# LED_Running_Final.net
KiCad netlist of a schematic drawn in Altium Designer
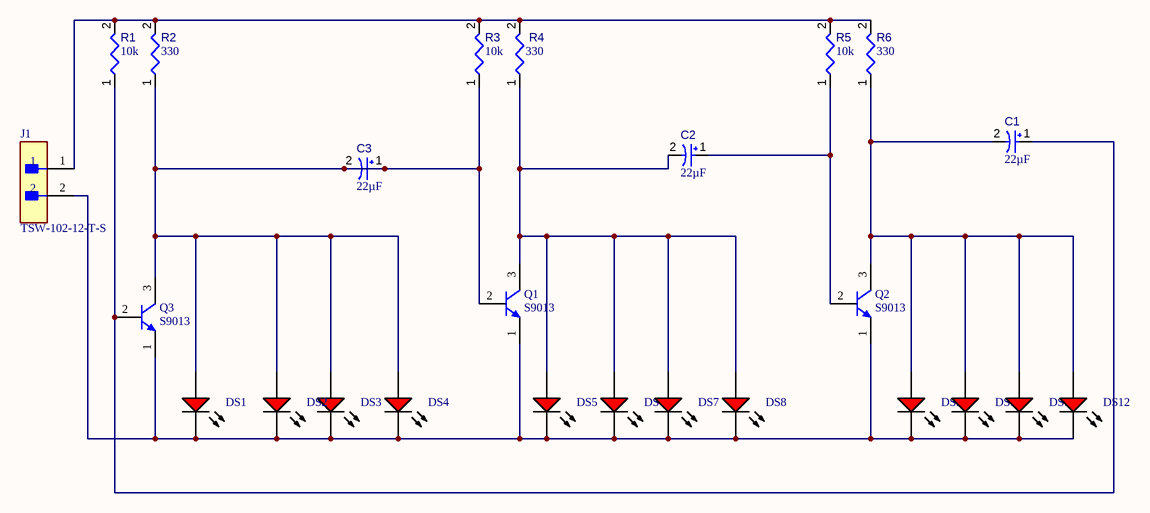
[diagram p0: LED_Running_Final.SchDoc]

(export (version "E")
  (design (tool "Eeschema 10.0.6"))
  (components
    (comp (ref "C1")
      (value "22µF")
      (footprint "CAPPR55-250-1120X630X1220")
      (description "Aluminum Electrolytic Capacitor, 22 uF, +/- 20%, 100 V, -40 to 85 degC, 2-Pin THD, RoHS, Bulk")
      (fields (field (name "MANUFACTURER") "Panasonic") (field (name "TOLERANCE") "20%"))
      (libsource (lib "MD RAFIUL ISLAM") (part "CAP-P-2"))
    )
    (comp (ref "C2")
      (value "22µF")
      (footprint "CAPPR55-250-1120X630X1220")
      (description "Aluminum Electrolytic Capacitor, 22 uF, +/- 20%, 100 V, -40 to 85 degC, 2-Pin THD, RoHS, Bulk")
      (fields (field (name "MANUFACTURER") "Panasonic") (field (name "TOLERANCE") "20%"))
      (libsource (lib "MD RAFIUL ISLAM") (part "CAP-P-2"))
    )
    (comp (ref "C3")
      (value "22µF")
      (footprint "CAPPR55-250-1120X630X1220")
      (description "Aluminum Electrolytic Capacitor, 22 uF, +/- 20%, 100 V, -40 to 85 degC, 2-Pin THD, RoHS, Bulk")
      (fields (field (name "MANUFACTURER") "Panasonic") (field (name "TOLERANCE") "20%"))
      (libsource (lib "MD RAFIUL ISLAM") (part "CAP-P-2"))
    )
    (comp (ref "DS1")
      (value "LTL-1CHE")
      (footprint "INDPR60-254-520X380X650")
      (description "LED Uni-Color Red, 100 mW, 30 mA, -55 to 100 degC, 2-Pin THD, RoHS, Bulk")
      (fields (field (name "MANUFACTURER") "Lite-On"))
      (libsource (lib "MD RAFIUL ISLAM") (part "LED-RED-AK-2"))
    )
    (comp (ref "DS2")
      (value "LTL-1CHE")
      (footprint "INDPR60-254-520X380X650")
      (description "LED Uni-Color Red, 100 mW, 30 mA, -55 to 100 degC, 2-Pin THD, RoHS, Bulk")
      (fields (field (name "MANUFACTURER") "Lite-On"))
      (libsource (lib "MD RAFIUL ISLAM") (part "LED-RED-AK-2"))
    )
    (comp (ref "DS3")
      (value "LTL-1CHE")
      (footprint "INDPR60-254-520X380X650")
      (description "LED Uni-Color Red, 100 mW, 30 mA, -55 to 100 degC, 2-Pin THD, RoHS, Bulk")
      (fields (field (name "MANUFACTURER") "Lite-On"))
      (libsource (lib "MD RAFIUL ISLAM") (part "LED-RED-AK-2"))
    )
    (comp (ref "DS4")
      (value "LTL-1CHE")
      (footprint "INDPR60-254-520X380X650")
      (description "LED Uni-Color Red, 100 mW, 30 mA, -55 to 100 degC, 2-Pin THD, RoHS, Bulk")
      (fields (field (name "MANUFACTURER") "Lite-On"))
      (libsource (lib "MD RAFIUL ISLAM") (part "LED-RED-AK-2"))
    )
    (comp (ref "DS5")
      (value "LTL-1CHE")
      (footprint "INDPR60-254-520X380X650")
      (description "LED Uni-Color Red, 100 mW, 30 mA, -55 to 100 degC, 2-Pin THD, RoHS, Bulk")
      (fields (field (name "MANUFACTURER") "Lite-On"))
      (libsource (lib "MD RAFIUL ISLAM") (part "LED-RED-AK-2"))
    )
    (comp (ref "DS6")
      (value "LTL-1CHE")
      (footprint "INDPR60-254-520X380X650")
      (description "LED Uni-Color Red, 100 mW, 30 mA, -55 to 100 degC, 2-Pin THD, RoHS, Bulk")
      (fields (field (name "MANUFACTURER") "Lite-On"))
      (libsource (lib "MD RAFIUL ISLAM") (part "LED-RED-AK-2"))
    )
    (comp (ref "DS7")
      (value "LTL-1CHE")
      (footprint "INDPR60-254-520X380X650")
      (description "LED Uni-Color Red, 100 mW, 30 mA, -55 to 100 degC, 2-Pin THD, RoHS, Bulk")
      (fields (field (name "MANUFACTURER") "Lite-On"))
      (libsource (lib "MD RAFIUL ISLAM") (part "LED-RED-AK-2"))
    )
    (comp (ref "DS8")
      (value "LTL-1CHE")
      (footprint "INDPR60-254-520X380X650")
      (description "LED Uni-Color Red, 100 mW, 30 mA, -55 to 100 degC, 2-Pin THD, RoHS, Bulk")
      (fields (field (name "MANUFACTURER") "Lite-On"))
      (libsource (lib "MD RAFIUL ISLAM") (part "LED-RED-AK-2"))
    )
    (comp (ref "DS9")
      (value "LTL-1CHE")
      (footprint "INDPR60-254-520X380X650")
      (description "LED Uni-Color Red, 100 mW, 30 mA, -55 to 100 degC, 2-Pin THD, RoHS, Bulk")
      (fields (field (name "MANUFACTURER") "Lite-On"))
      (libsource (lib "MD RAFIUL ISLAM") (part "LED-RED-AK-2"))
    )
    (comp (ref "DS10")
      (value "LTL-1CHE")
      (footprint "INDPR60-254-520X380X650")
      (description "LED Uni-Color Red, 100 mW, 30 mA, -55 to 100 degC, 2-Pin THD, RoHS, Bulk")
      (fields (field (name "MANUFACTURER") "Lite-On"))
      (libsource (lib "MD RAFIUL ISLAM") (part "LED-RED-AK-2"))
    )
    (comp (ref "DS11")
      (value "LTL-1CHE")
      (footprint "INDPR60-254-520X380X650")
      (description "LED Uni-Color Red, 100 mW, 30 mA, -55 to 100 degC, 2-Pin THD, RoHS, Bulk")
      (fields (field (name "MANUFACTURER") "Lite-On"))
      (libsource (lib "MD RAFIUL ISLAM") (part "LED-RED-AK-2"))
    )
    (comp (ref "DS12")
      (value "LTL-1CHE")
      (footprint "INDPR60-254-520X380X650")
      (description "LED Uni-Color Red, 100 mW, 30 mA, -55 to 100 degC, 2-Pin THD, RoHS, Bulk")
      (fields (field (name "MANUFACTURER") "Lite-On"))
      (libsource (lib "MD RAFIUL ISLAM") (part "LED-RED-AK-2"))
    )
    (comp (ref "J1")
      (value "TSW-102-12-T-S")
      (footprint "FP-TSW-102-12-T-S-MFG")
      (description "CONN HEADER VERT 2POS 2.54MM")
      (libsource (lib "Altium Content Vault") (part "3bc925449376181038e59eaffc5286c"))
    )
    (comp (ref "Q1")
      (value "S9013")
      (footprint "JSCJ-TO-92-3_V")
      (description "Transistor, NPN, 0.1 uA, 150 MHz, 3-Pin TO-92")
      (fields (field (name "MANUFACTURER") "Jiangsu Changjiang Electronics Technology"))
      (libsource (lib "MD RAFIUL ISLAM") (part "BJT-NPN-EBC-3"))
    )
    (comp (ref "Q2")
      (value "S9013")
      (footprint "JSCJ-TO-92-3_V")
      (description "Transistor, NPN, 0.1 uA, 150 MHz, 3-Pin TO-92")
      (fields (field (name "MANUFACTURER") "Jiangsu Changjiang Electronics Technology"))
      (libsource (lib "MD RAFIUL ISLAM") (part "BJT-NPN-EBC-3"))
    )
    (comp (ref "Q3")
      (value "S9013")
      (footprint "JSCJ-TO-92-3_V")
      (description "Transistor, NPN, 0.1 uA, 150 MHz, 3-Pin TO-92")
      (fields (field (name "MANUFACTURER") "Jiangsu Changjiang Electronics Technology"))
      (libsource (lib "MD RAFIUL ISLAM") (part "BJT-NPN-EBC-3"))
    )
    (comp (ref "R1")
      (value "10k")
      (footprint "RESA60-630X240")
      (description "Axial Resistor, 10 KOhm, +/- 1%, 0.25 W, -55 to 155 degC, 2-Pin THD, RoHS, Bulk")
      (fields (field (name "TOLERANCE") "1%") (field (name "POWER") "250mW"))
      (libsource (lib "MD RAFIUL ISLAM") (part "RES-2"))
    )
    (comp (ref "R2")
      (value "330")
      (footprint "BGA81C100P9X9_1100X1100X350M")
      (description "Fixed Resistor, Carbon Film, 0.125W, 330ohm, 250V, 5% +/-Tol, -400, 0ppm/Cel, Through Hole Mount")
      (fields (field (name "TOLERANCE") "5%") (field (name "Comment") "CF18JT330R"))
      (libsource (lib "MD RAFIUL ISLAM") (part "RES-2"))
    )
    (comp (ref "R3")
      (value "10k")
      (footprint "RESA60-630X240")
      (description "Axial Resistor, 10 KOhm, +/- 1%, 0.25 W, -55 to 155 degC, 2-Pin THD, RoHS, Bulk")
      (fields (field (name "TOLERANCE") "1%") (field (name "POWER") "250mW"))
      (libsource (lib "MD RAFIUL ISLAM") (part "RES-2"))
    )
    (comp (ref "R4")
      (value "330")
      (footprint "BGA81C100P9X9_1100X1100X350M")
      (description "Fixed Resistor, Carbon Film, 0.125W, 330ohm, 250V, 5% +/-Tol, -400, 0ppm/Cel, Through Hole Mount")
      (fields (field (name "TOLERANCE") "5%") (field (name "Comment") "CF18JT330R"))
      (libsource (lib "MD RAFIUL ISLAM") (part "RES-2"))
    )
    (comp (ref "R5")
      (value "10k")
      (footprint "RESA60-630X240")
      (description "Axial Resistor, 10 KOhm, +/- 1%, 0.25 W, -55 to 155 degC, 2-Pin THD, RoHS, Bulk")
      (fields (field (name "TOLERANCE") "1%") (field (name "POWER") "250mW"))
      (libsource (lib "MD RAFIUL ISLAM") (part "RES-2"))
    )
    (comp (ref "R6")
      (value "330")
      (footprint "BGA81C100P9X9_1100X1100X350M")
      (description "Fixed Resistor, Carbon Film, 0.125W, 330ohm, 250V, 5% +/-Tol, -400, 0ppm/Cel, Through Hole Mount")
      (fields (field (name "TOLERANCE") "5%") (field (name "Comment") "CF18JT330R"))
      (libsource (lib "MD RAFIUL ISLAM") (part "RES-2"))
    )
  )
  (nets
    (net (code "1") (name "Net-(DS1-A)") (class "Default")
      (node (ref "C3") (pin "1") (pinfunction "1_1") (pintype "passive"))
      (node (ref "C3") (pin "2") (pinfunction "2_2") (pintype "passive"))
      (node (ref "DS1") (pin "1") (pinfunction "A_1") (pintype "passive"))
      (node (ref "DS2") (pin "1") (pinfunction "A_1") (pintype "passive"))
      (node (ref "DS3") (pin "1") (pinfunction "A_1") (pintype "passive"))
      (node (ref "DS4") (pin "1") (pinfunction "A_1") (pintype "passive"))
      (node (ref "Q1") (pin "2") (pinfunction "B_2") (pintype "passive"))
      (node (ref "Q3") (pin "3") (pinfunction "C_3") (pintype "passive"))
      (node (ref "R2") (pin "1") (pinfunction "1_1") (pintype "passive"))
      (node (ref "R3") (pin "1") (pinfunction "1_1") (pintype "passive"))
    )
    (net (code "2") (name "Net-(DS1-K)") (class "Default")
      (node (ref "DS1") (pin "2") (pinfunction "K_2") (pintype "passive"))
      (node (ref "DS10") (pin "2") (pinfunction "K_2") (pintype "passive"))
      (node (ref "DS11") (pin "2") (pinfunction "K_2") (pintype "passive"))
      (node (ref "DS12") (pin "2") (pinfunction "K_2") (pintype "passive"))
      (node (ref "DS2") (pin "2") (pinfunction "K_2") (pintype "passive"))
      (node (ref "DS3") (pin "2") (pinfunction "K_2") (pintype "passive"))
      (node (ref "DS4") (pin "2") (pinfunction "K_2") (pintype "passive"))
      (node (ref "DS5") (pin "2") (pinfunction "K_2") (pintype "passive"))
      (node (ref "DS6") (pin "2") (pinfunction "K_2") (pintype "passive"))
      (node (ref "DS7") (pin "2") (pinfunction "K_2") (pintype "passive"))
      (node (ref "DS8") (pin "2") (pinfunction "K_2") (pintype "passive"))
      (node (ref "DS9") (pin "2") (pinfunction "K_2") (pintype "passive"))
      (node (ref "J1") (pin "2") (pinfunction "2_2") (pintype "passive"))
      (node (ref "Q1") (pin "1") (pinfunction "E_1") (pintype "passive"))
      (node (ref "Q2") (pin "1") (pinfunction "E_1") (pintype "passive"))
      (node (ref "Q3") (pin "1") (pinfunction "E_1") (pintype "passive"))
    )
    (net (code "3") (name "Net-(DS5-A)") (class "Default")
      (node (ref "C2") (pin "2") (pinfunction "2_2") (pintype "passive"))
      (node (ref "DS5") (pin "1") (pinfunction "A_1") (pintype "passive"))
      (node (ref "DS6") (pin "1") (pinfunction "A_1") (pintype "passive"))
      (node (ref "DS7") (pin "1") (pinfunction "A_1") (pintype "passive"))
      (node (ref "DS8") (pin "1") (pinfunction "A_1") (pintype "passive"))
      (node (ref "Q1") (pin "3") (pinfunction "C_3") (pintype "passive"))
      (node (ref "R4") (pin "1") (pinfunction "1_1") (pintype "passive"))
    )
    (net (code "4") (name "Net-(DS10-A)") (class "Default")
      (node (ref "C1") (pin "2") (pinfunction "2_2") (pintype "passive"))
      (node (ref "DS10") (pin "1") (pinfunction "A_1") (pintype "passive"))
      (node (ref "DS11") (pin "1") (pinfunction "A_1") (pintype "passive"))
      (node (ref "DS12") (pin "1") (pinfunction "A_1") (pintype "passive"))
      (node (ref "DS9") (pin "1") (pinfunction "A_1") (pintype "passive"))
      (node (ref "Q2") (pin "3") (pinfunction "C_3") (pintype "passive"))
      (node (ref "R6") (pin "1") (pinfunction "1_1") (pintype "passive"))
    )
    (net (code "5") (name "Net-(J1-Pad1)") (class "Default")
      (node (ref "J1") (pin "1") (pinfunction "1_1") (pintype "passive"))
      (node (ref "R1") (pin "2") (pinfunction "2_2") (pintype "passive"))
      (node (ref "R2") (pin "2") (pinfunction "2_2") (pintype "passive"))
      (node (ref "R3") (pin "2") (pinfunction "2_2") (pintype "passive"))
      (node (ref "R4") (pin "2") (pinfunction "2_2") (pintype "passive"))
      (node (ref "R5") (pin "2") (pinfunction "2_2") (pintype "passive"))
      (node (ref "R6") (pin "2") (pinfunction "2_2") (pintype "passive"))
    )
    (net (code "6") (name "Net-(Q2-B)") (class "Default")
      (node (ref "C2") (pin "1") (pinfunction "1_1") (pintype "passive"))
      (node (ref "Q2") (pin "2") (pinfunction "B_2") (pintype "passive"))
      (node (ref "R5") (pin "1") (pinfunction "1_1") (pintype "passive"))
    )
    (net (code "7") (name "Net-(Q3-B)") (class "Default")
      (node (ref "C1") (pin "1") (pinfunction "1_1") (pintype "passive"))
      (node (ref "Q3") (pin "2") (pinfunction "B_2") (pintype "passive"))
      (node (ref "R1") (pin "1") (pinfunction "1_1") (pintype "passive"))
    )
  )
)
